# Course_Design.net
KiCad netlist of a schematic drawn in Altium Designer
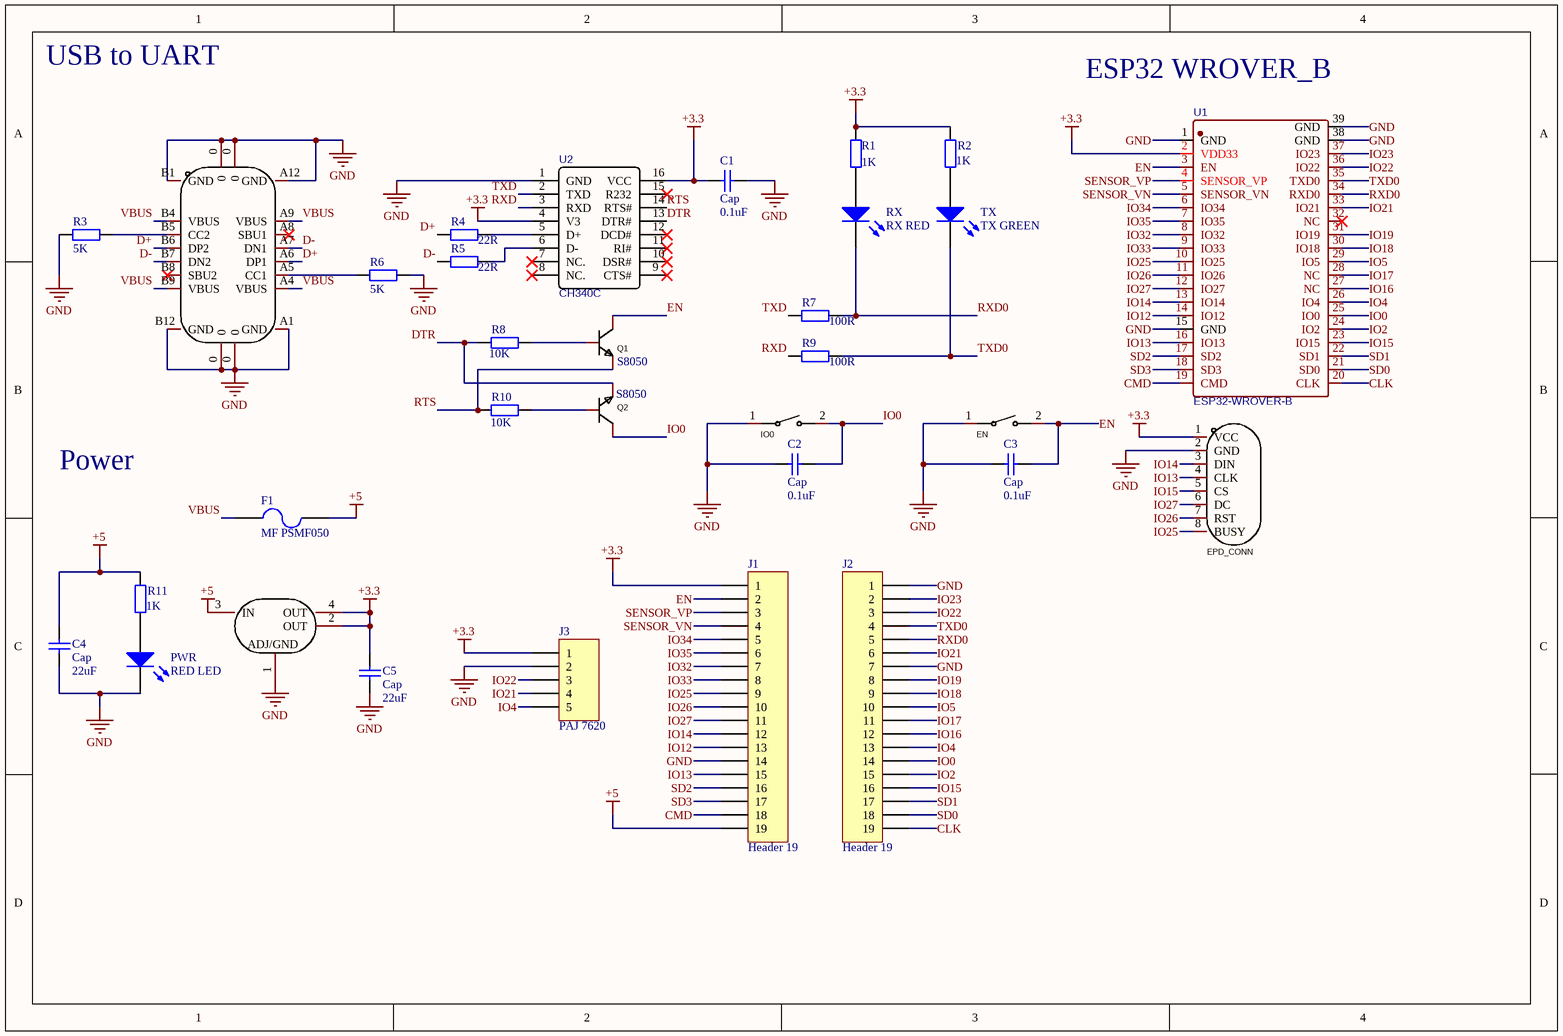
[diagram p0: Course Design.SchDoc]

(export (version "E")
  (design (tool "Eeschema 10.0.6"))
  (components
    (comp (ref "C1")
      (value "Cap")
      (footprint "电容:0805C")
      (description "Capacitor")
      (fields (field (name "ALTIUM_VALUE") "0.1uF") (field (name "PUBLISHER") "Altium Limited"))
      (libsource (lib "Miscellaneous Devices") (part "Cap"))
    )
    (comp (ref "C2")
      (value "Cap")
      (footprint "电容:0805C")
      (description "Capacitor")
      (fields (field (name "ALTIUM_VALUE") "0.1uF") (field (name "PUBLISHER") "Altium Limited"))
      (libsource (lib "Miscellaneous Devices") (part "Cap"))
    )
    (comp (ref "C3")
      (value "Cap")
      (footprint "电容:0805C")
      (description "Capacitor")
      (fields (field (name "ALTIUM_VALUE") "0.1uF") (field (name "PUBLISHER") "Altium Limited"))
      (libsource (lib "Miscellaneous Devices") (part "Cap"))
    )
    (comp (ref "C4")
      (value "Cap")
      (footprint "电容:1206C")
      (description "Capacitor")
      (fields (field (name "ALTIUM_VALUE") "22uF") (field (name "PUBLISHER") "Altium Limited"))
      (libsource (lib "Miscellaneous Devices") (part "Cap"))
    )
    (comp (ref "C5")
      (value "Cap")
      (footprint "电容:1206C")
      (description "Capacitor")
      (fields (field (name "ALTIUM_VALUE") "22uF") (field (name "PUBLISHER") "Altium Limited"))
      (libsource (lib "Miscellaneous Devices") (part "Cap"))
    )
    (comp (ref "EN")
      (value "K2-1107ST-A4DW-06_C118141")
      (footprint "KEY-SMD_L6.2-W3.6-LS8.0")
      (fields (field (name "MANUFACTURER") "韩国韩荣") (field (name "MANUFACTURER PART") "K2-1107ST-A4DW-06"))
      (libsource (lib "Schlib1") (part "K2-1107ST-A4DW-06_C118141"))
    )
    (comp (ref "EPD_CONN")
      (value "X2012WV-08-N0SN")
      (footprint "CONN-TH_X2012WV-08-N0SN")
      (fields (field (name "MANUFACTURER") "XKB Connectivity(中国星坤)"))
      (libsource (lib "Schlib1") (part "X2012WV-08-N0SN"))
    )
    (comp (ref "F1")
      (value "MF PSMF050")
      (footprint "0805")
      (description "Fuse")
      (fields (field (name "PUBLISHER") "Altium Limited"))
      (libsource (lib "Miscellaneous Devices") (part "Fuse 2"))
    )
    (comp (ref "IO0")
      (value "K2-1107ST-A4DW-06_C118141")
      (footprint "KEY-SMD_L6.2-W3.6-LS8.0")
      (fields (field (name "MANUFACTURER") "韩国韩荣") (field (name "MANUFACTURER PART") "K2-1107ST-A4DW-06"))
      (libsource (lib "Schlib1") (part "K2-1107ST-A4DW-06_C118141"))
    )
    (comp (ref "J1")
      (value "Header 19")
      (footprint "HDR1X19")
      (description "Header, 19-Pin")
      (fields (field (name "PUBLISHER") "Altium Limited"))
      (libsource (lib "Miscellaneous Connectors") (part "Header 19"))
    )
    (comp (ref "J2")
      (value "Header 19")
      (footprint "HDR1X19")
      (description "Header, 19-Pin")
      (fields (field (name "PUBLISHER") "Altium Limited"))
      (libsource (lib "") (part "Header 19_1"))
    )
    (comp (ref "J3")
      (value "PAJ 7620")
      (footprint "PAJ7620")
      (description "Header, 5-Pin")
      (fields (field (name "PUBLISHER") "Altium Limited"))
      (libsource (lib "Miscellaneous Connectors") (part "Header 5"))
    )
    (comp (ref "PWR")
      (value "RED LED")
      (footprint "0805D")
      (description "Typical INFRARED GaAs LED")
      (fields (field (name "PUBLISHER") "Altium Limited"))
      (libsource (lib "Miscellaneous Devices") (part "LED0"))
    )
    (comp (ref "Q1")
      (value "S8050")
      (footprint "SOT23_N")
      (fields (field (name "MANUFACTURER") "Doeshare(德芯)"))
      (libsource (lib "Schlib1") (part "S8050"))
    )
    (comp (ref "Q2")
      (value "S8050")
      (footprint "SOT23_N")
      (fields (field (name "MANUFACTURER") "Doeshare(德芯)"))
      (libsource (lib "Schlib1") (part "S8050"))
    )
    (comp (ref "R1")
      (value "1K")
      (footprint "0805R")
      (description "Resistor")
      (fields (field (name "Comment") "Res2") (field (name "PUBLISHER") "Altium Limited"))
      (libsource (lib "Miscellaneous Devices") (part "Res2"))
    )
    (comp (ref "R2")
      (value "1K")
      (footprint "0805R")
      (description "Resistor")
      (fields (field (name "Comment") "Res2") (field (name "PUBLISHER") "Altium Limited"))
      (libsource (lib "Miscellaneous Devices") (part "Res2"))
    )
    (comp (ref "R3")
      (value "5K")
      (footprint "0805R")
      (description "Resistor")
      (fields (field (name "Comment") "Res2") (field (name "PUBLISHER") "Altium Limited"))
      (libsource (lib "") (part "Res2_1"))
    )
    (comp (ref "R4")
      (value "22R")
      (footprint "0805R")
      (description "Resistor")
      (fields (field (name "Comment") "Res2") (field (name "PUBLISHER") "Altium Limited"))
      (libsource (lib "") (part "Res2_1"))
    )
    (comp (ref "R5")
      (value "22R")
      (footprint "0805R")
      (description "Resistor")
      (fields (field (name "Comment") "Res2") (field (name "PUBLISHER") "Altium Limited"))
      (libsource (lib "") (part "Res2_1"))
    )
    (comp (ref "R6")
      (value "5K")
      (footprint "0805R")
      (description "Resistor")
      (fields (field (name "Comment") "Res2") (field (name "PUBLISHER") "Altium Limited"))
      (libsource (lib "") (part "Res2_1"))
    )
    (comp (ref "R7")
      (value "100R")
      (footprint "0805R")
      (description "Resistor")
      (fields (field (name "Comment") "Res2") (field (name "PUBLISHER") "Altium Limited"))
      (libsource (lib "") (part "Res2_1"))
    )
    (comp (ref "R8")
      (value "10K")
      (footprint "0805R")
      (description "Resistor")
      (fields (field (name "Comment") "Res2") (field (name "PUBLISHER") "Altium Limited"))
      (libsource (lib "") (part "Res2_1"))
    )
    (comp (ref "R9")
      (value "100R")
      (footprint "0805R")
      (description "Resistor")
      (fields (field (name "Comment") "Res2") (field (name "PUBLISHER") "Altium Limited"))
      (libsource (lib "") (part "Res2_1"))
    )
    (comp (ref "R10")
      (value "10K")
      (footprint "0805R")
      (description "Resistor")
      (fields (field (name "Comment") "Res2") (field (name "PUBLISHER") "Altium Limited"))
      (libsource (lib "") (part "Res2_1"))
    )
    (comp (ref "R11")
      (value "1K")
      (footprint "0805R")
      (description "Resistor")
      (fields (field (name "Comment") "Res2") (field (name "PUBLISHER") "Altium Limited"))
      (libsource (lib "Miscellaneous Devices") (part "Res2"))
    )
    (comp (ref "RX")
      (value "RX RED")
      (footprint "0805D")
      (description "Typical INFRARED GaAs LED")
      (fields (field (name "PUBLISHER") "Altium Limited"))
      (libsource (lib "Miscellaneous Devices") (part "LED0"))
    )
    (comp (ref "TX")
      (value "TX GREEN")
      (footprint "0805D")
      (description "Typical INFRARED GaAs LED")
      (fields (field (name "PUBLISHER") "Altium Limited"))
      (libsource (lib "Miscellaneous Devices") (part "LED0"))
    )
    (comp (ref "U1")
      (value "ESP32-WROVER-B")
      (footprint "ESP32 WROVER B")
      (fields (field (name "BOM_SUPPLIER PART") "C503591") (field (name "CONTRIBUTOR") "LCSC"))
      (libsource (lib "Schlib1") (part "ESP32-WROVER-B"))
    )
    (comp (ref "U2")
      (value "CH340C")
      (footprint "SOP-16_L10.0")
      (fields (field (name "BOM_SUPPLIER PART") "C84681"))
      (libsource (lib "Schlib1") (part "CH340C"))
    )
    (comp (ref "U3")
      (value "AMS1117-3.3_C2992570")
      (footprint "SOT223_N")
      (fields (field (name "MANUFACTURER") "国芯佳品") (field (name "MANUFACTURER PART") "AMS1117-3.3"))
      (libsource (lib "Schlib1") (part "AMS1117-3.3_C2992570"))
    )
    (comp (ref "USBC1")
      (value "TYPE-C-31-M-12")
      (footprint "USB-C_SMD")
      (fields (field (name "MANUFACTURER") "韩国韩荣"))
      (libsource (lib "Schlib1") (part "TYPE-C-31-M-12"))
    )
  )
  (nets
    (net (code "1") (name "+3.3") (class "Default")
      (node (ref "C1") (pin "1") (pinfunction "1_1") (pintype "passive"))
      (node (ref "C5") (pin "2") (pinfunction "2_2") (pintype "passive"))
      (node (ref "EPD_CONN") (pin "1") (pinfunction "VCC_1") (pintype "passive"))
      (node (ref "J1") (pin "1") (pinfunction "1_1") (pintype "passive"))
      (node (ref "J3") (pin "1") (pinfunction "1_1") (pintype "passive"))
      (node (ref "R1") (pin "2") (pinfunction "2_2") (pintype "passive"))
      (node (ref "R2") (pin "2") (pinfunction "2_2") (pintype "passive"))
      (node (ref "U1") (pin "2") (pinfunction "VDD33_2") (pintype "passive"))
      (node (ref "U2") (pin "16") (pinfunction "VCC_16") (pintype "passive"))
      (node (ref "U2") (pin "4") (pinfunction "V3_4") (pintype "passive"))
      (node (ref "U3") (pin "2") (pinfunction "OUT_2") (pintype "passive"))
      (node (ref "U3") (pin "4") (pinfunction "OUT_4") (pintype "passive"))
    )
    (net (code "2") (name "+5") (class "Default")
      (node (ref "C4") (pin "2") (pinfunction "2_2") (pintype "passive"))
      (node (ref "F1") (pin "2") (pinfunction "2_2") (pintype "passive"))
      (node (ref "J1") (pin "19") (pinfunction "19_19") (pintype "passive"))
      (node (ref "R11") (pin "2") (pinfunction "2_2") (pintype "passive"))
      (node (ref "U3") (pin "3") (pinfunction "IN_3") (pintype "passive"))
    )
    (net (code "3") (name "/CLK") (class "Default")
      (node (ref "J2") (pin "19") (pinfunction "19_19") (pintype "passive"))
      (node (ref "U1") (pin "20") (pinfunction "CLK_20") (pintype "passive"))
    )
    (net (code "4") (name "/CMD") (class "Default")
      (node (ref "J1") (pin "18") (pinfunction "18_18") (pintype "passive"))
      (node (ref "U1") (pin "19") (pinfunction "CMD_19") (pintype "passive"))
    )
    (net (code "5") (name "/D+") (class "Default")
      (node (ref "R4") (pin "1") (pinfunction "1_1") (pintype "passive"))
      (node (ref "USBC1") (pin "A6") (pinfunction "DP1_A6") (pintype "passive"))
      (node (ref "USBC1") (pin "B6") (pinfunction "DP2_B6") (pintype "passive"))
    )
    (net (code "6") (name "/D-") (class "Default")
      (node (ref "R5") (pin "1") (pinfunction "1_1") (pintype "passive"))
      (node (ref "USBC1") (pin "A7") (pinfunction "DN1_A7") (pintype "passive"))
      (node (ref "USBC1") (pin "B7") (pinfunction "DN2_B7") (pintype "passive"))
    )
    (net (code "7") (name "/DTR") (class "Default")
      (node (ref "Q2") (pin "2") (pinfunction "E_2") (pintype "passive"))
      (node (ref "R8") (pin "1") (pinfunction "1_1") (pintype "passive"))
      (node (ref "U2") (pin "13") (pinfunction "DTR#_13") (pintype "passive"))
    )
    (net (code "8") (name "/EN") (class "Default")
      (node (ref "C3") (pin "2") (pinfunction "2_2") (pintype "passive"))
      (node (ref "EN") (pin "2") (pinfunction "2_2") (pintype "passive"))
      (node (ref "J1") (pin "2") (pinfunction "2_2") (pintype "passive"))
      (node (ref "Q1") (pin "3") (pinfunction "C_3") (pintype "passive"))
      (node (ref "U1") (pin "3") (pinfunction "EN_3") (pintype "passive"))
    )
    (net (code "9") (name "/IO0") (class "Default")
      (node (ref "C2") (pin "2") (pinfunction "2_2") (pintype "passive"))
      (node (ref "IO0") (pin "2") (pinfunction "2_2") (pintype "passive"))
      (node (ref "J2") (pin "14") (pinfunction "14_14") (pintype "passive"))
      (node (ref "Q2") (pin "3") (pinfunction "C_3") (pintype "passive"))
      (node (ref "U1") (pin "25") (pinfunction "IO0_25") (pintype "passive"))
    )
    (net (code "10") (name "/IO2") (class "Default")
      (node (ref "J2") (pin "15") (pinfunction "15_15") (pintype "passive"))
      (node (ref "U1") (pin "24") (pinfunction "IO2_24") (pintype "passive"))
    )
    (net (code "11") (name "/IO4") (class "Default")
      (node (ref "J2") (pin "13") (pinfunction "13_13") (pintype "passive"))
      (node (ref "J3") (pin "5") (pinfunction "5_5") (pintype "passive"))
      (node (ref "U1") (pin "26") (pinfunction "IO4_26") (pintype "passive"))
    )
    (net (code "12") (name "/IO5") (class "Default")
      (node (ref "J2") (pin "10") (pinfunction "10_10") (pintype "passive"))
      (node (ref "U1") (pin "29") (pinfunction "IO5_29") (pintype "passive"))
    )
    (net (code "13") (name "/IO12") (class "Default")
      (node (ref "J1") (pin "13") (pinfunction "13_13") (pintype "passive"))
      (node (ref "U1") (pin "14") (pinfunction "IO12_14") (pintype "passive"))
    )
    (net (code "14") (name "/IO13") (class "Default")
      (node (ref "EPD_CONN") (pin "4") (pinfunction "CLK_4") (pintype "passive"))
      (node (ref "J1") (pin "15") (pinfunction "15_15") (pintype "passive"))
      (node (ref "U1") (pin "16") (pinfunction "IO13_16") (pintype "passive"))
    )
    (net (code "15") (name "/IO14") (class "Default")
      (node (ref "EPD_CONN") (pin "3") (pinfunction "DIN_3") (pintype "passive"))
      (node (ref "J1") (pin "12") (pinfunction "12_12") (pintype "passive"))
      (node (ref "U1") (pin "13") (pinfunction "IO14_13") (pintype "passive"))
    )
    (net (code "16") (name "/IO15") (class "Default")
      (node (ref "EPD_CONN") (pin "5") (pinfunction "CS_5") (pintype "passive"))
      (node (ref "J2") (pin "16") (pinfunction "16_16") (pintype "passive"))
      (node (ref "U1") (pin "23") (pinfunction "IO15_23") (pintype "passive"))
    )
    (net (code "17") (name "/IO16") (class "Default")
      (node (ref "J2") (pin "12") (pinfunction "12_12") (pintype "passive"))
      (node (ref "U1") (pin "27") (pinfunction "NC_27") (pintype "passive"))
    )
    (net (code "18") (name "/IO17") (class "Default")
      (node (ref "J2") (pin "11") (pinfunction "11_11") (pintype "passive"))
      (node (ref "U1") (pin "28") (pinfunction "NC_28") (pintype "passive"))
    )
    (net (code "19") (name "/IO18") (class "Default")
      (node (ref "J2") (pin "9") (pinfunction "9_9") (pintype "passive"))
      (node (ref "U1") (pin "30") (pinfunction "IO18_30") (pintype "passive"))
    )
    (net (code "20") (name "/IO19") (class "Default")
      (node (ref "J2") (pin "8") (pinfunction "8_8") (pintype "passive"))
      (node (ref "U1") (pin "31") (pinfunction "IO19_31") (pintype "passive"))
    )
    (net (code "21") (name "/IO21") (class "Default")
      (node (ref "J2") (pin "6") (pinfunction "6_6") (pintype "passive"))
      (node (ref "J3") (pin "4") (pinfunction "4_4") (pintype "passive"))
      (node (ref "U1") (pin "33") (pinfunction "IO21_33") (pintype "passive"))
    )
    (net (code "22") (name "/IO22") (class "Default")
      (node (ref "J2") (pin "3") (pinfunction "3_3") (pintype "passive"))
      (node (ref "J3") (pin "3") (pinfunction "3_3") (pintype "passive"))
      (node (ref "U1") (pin "36") (pinfunction "IO22_36") (pintype "passive"))
    )
    (net (code "23") (name "/IO23") (class "Default")
      (node (ref "J2") (pin "2") (pinfunction "2_2") (pintype "passive"))
      (node (ref "U1") (pin "37") (pinfunction "IO23_37") (pintype "passive"))
    )
    (net (code "24") (name "/IO25") (class "Default")
      (node (ref "EPD_CONN") (pin "8") (pinfunction "BUSY_8") (pintype "passive"))
      (node (ref "J1") (pin "9") (pinfunction "9_9") (pintype "passive"))
      (node (ref "U1") (pin "10") (pinfunction "IO25_10") (pintype "passive"))
    )
    (net (code "25") (name "/IO26") (class "Default")
      (node (ref "EPD_CONN") (pin "7") (pinfunction "RST_7") (pintype "passive"))
      (node (ref "J1") (pin "10") (pinfunction "10_10") (pintype "passive"))
      (node (ref "U1") (pin "11") (pinfunction "IO26_11") (pintype "passive"))
    )
    (net (code "26") (name "/IO27") (class "Default")
      (node (ref "EPD_CONN") (pin "6") (pinfunction "DC_6") (pintype "passive"))
      (node (ref "J1") (pin "11") (pinfunction "11_11") (pintype "passive"))
      (node (ref "U1") (pin "12") (pinfunction "IO27_12") (pintype "passive"))
    )
    (net (code "27") (name "/IO32") (class "Default")
      (node (ref "J1") (pin "7") (pinfunction "7_7") (pintype "passive"))
      (node (ref "U1") (pin "8") (pinfunction "IO32_8") (pintype "passive"))
    )
    (net (code "28") (name "/IO33") (class "Default")
      (node (ref "J1") (pin "8") (pinfunction "8_8") (pintype "passive"))
      (node (ref "U1") (pin "9") (pinfunction "IO33_9") (pintype "passive"))
    )
    (net (code "29") (name "/IO34") (class "Default")
      (node (ref "J1") (pin "5") (pinfunction "5_5") (pintype "passive"))
      (node (ref "U1") (pin "6") (pinfunction "IO34_6") (pintype "passive"))
    )
    (net (code "30") (name "/IO35") (class "Default")
      (node (ref "J1") (pin "6") (pinfunction "6_6") (pintype "passive"))
      (node (ref "U1") (pin "7") (pinfunction "IO35_7") (pintype "passive"))
    )
    (net (code "31") (name "/RTS") (class "Default")
      (node (ref "Q1") (pin "2") (pinfunction "E_2") (pintype "passive"))
      (node (ref "R10") (pin "1") (pinfunction "1_1") (pintype "passive"))
      (node (ref "U2") (pin "14") (pinfunction "RTS#_14") (pintype "passive"))
    )
    (net (code "32") (name "/RXD") (class "Default")
      (node (ref "R9") (pin "1") (pinfunction "1_1") (pintype "passive"))
      (node (ref "U2") (pin "3") (pinfunction "RXD_3") (pintype "passive"))
    )
    (net (code "33") (name "/RXD0") (class "Default")
      (node (ref "J2") (pin "5") (pinfunction "5_5") (pintype "passive"))
      (node (ref "R7") (pin "2") (pinfunction "2_2") (pintype "passive"))
      (node (ref "RX") (pin "2") (pinfunction "K_2") (pintype "passive"))
      (node (ref "U1") (pin "34") (pinfunction "RXD0_34") (pintype "passive"))
    )
    (net (code "34") (name "/SD0") (class "Default")
      (node (ref "J2") (pin "18") (pinfunction "18_18") (pintype "passive"))
      (node (ref "U1") (pin "21") (pinfunction "SD0_21") (pintype "passive"))
    )
    (net (code "35") (name "/SD1") (class "Default")
      (node (ref "J2") (pin "17") (pinfunction "17_17") (pintype "passive"))
      (node (ref "U1") (pin "22") (pinfunction "SD1_22") (pintype "passive"))
    )
    (net (code "36") (name "/SD2") (class "Default")
      (node (ref "J1") (pin "16") (pinfunction "16_16") (pintype "passive"))
      (node (ref "U1") (pin "17") (pinfunction "SD2_17") (pintype "passive"))
    )
    (net (code "37") (name "/SD3") (class "Default")
      (node (ref "J1") (pin "17") (pinfunction "17_17") (pintype "passive"))
      (node (ref "U1") (pin "18") (pinfunction "SD3_18") (pintype "passive"))
    )
    (net (code "38") (name "/SENSOR_VN") (class "Default")
      (node (ref "J1") (pin "4") (pinfunction "4_4") (pintype "passive"))
      (node (ref "U1") (pin "5") (pinfunction "SENSOR_VN_5") (pintype "passive"))
    )
    (net (code "39") (name "/SENSOR_VP") (class "Default")
      (node (ref "J1") (pin "3") (pinfunction "3_3") (pintype "passive"))
      (node (ref "U1") (pin "4") (pinfunction "SENSOR_VP_4") (pintype "passive"))
    )
    (net (code "40") (name "/TXD") (class "Default")
      (node (ref "R7") (pin "1") (pinfunction "1_1") (pintype "passive"))
      (node (ref "U2") (pin "2") (pinfunction "TXD_2") (pintype "passive"))
    )
    (net (code "41") (name "/TXD0") (class "Default")
      (node (ref "J2") (pin "4") (pinfunction "4_4") (pintype "passive"))
      (node (ref "R9") (pin "2") (pinfunction "2_2") (pintype "passive"))
      (node (ref "TX") (pin "2") (pinfunction "K_2") (pintype "passive"))
      (node (ref "U1") (pin "35") (pinfunction "TXD0_35") (pintype "passive"))
    )
    (net (code "42") (name "/VBUS") (class "Default")
      (node (ref "F1") (pin "1") (pinfunction "1_1") (pintype "passive"))
      (node (ref "USBC1") (pin "A4") (pinfunction "VBUS_A4") (pintype "passive"))
      (node (ref "USBC1") (pin "A9") (pinfunction "VBUS_A9") (pintype "passive"))
      (node (ref "USBC1") (pin "B4") (pinfunction "VBUS_B4") (pintype "passive"))
      (node (ref "USBC1") (pin "B9") (pinfunction "VBUS_B9") (pintype "passive"))
    )
    (net (code "43") (name "GND") (class "Default")
      (node (ref "C1") (pin "2") (pinfunction "2_2") (pintype "passive"))
      (node (ref "C2") (pin "1") (pinfunction "1_1") (pintype "passive"))
      (node (ref "C3") (pin "1") (pinfunction "1_1") (pintype "passive"))
      (node (ref "C4") (pin "1") (pinfunction "1_1") (pintype "passive"))
      (node (ref "C5") (pin "1") (pinfunction "1_1") (pintype "passive"))
      (node (ref "EN") (pin "1") (pinfunction "1_1") (pintype "passive"))
      (node (ref "EPD_CONN") (pin "2") (pinfunction "GND_2") (pintype "passive"))
      (node (ref "IO0") (pin "1") (pinfunction "1_1") (pintype "passive"))
      (node (ref "J1") (pin "14") (pinfunction "14_14") (pintype "passive"))
      (node (ref "J2") (pin "1") (pinfunction "1_1") (pintype "passive"))
      (node (ref "J2") (pin "7") (pinfunction "7_7") (pintype "passive"))
      (node (ref "J3") (pin "2") (pinfunction "2_2") (pintype "passive"))
      (node (ref "PWR") (pin "2") (pinfunction "K_2") (pintype "passive"))
      (node (ref "R3") (pin "1") (pinfunction "1_1") (pintype "passive"))
      (node (ref "R6") (pin "2") (pinfunction "2_2") (pintype "passive"))
      (node (ref "U1") (pin "1") (pinfunction "GND_1") (pintype "passive"))
      (node (ref "U1") (pin "15") (pinfunction "GND_15") (pintype "passive"))
      (node (ref "U1") (pin "38") (pinfunction "GND_38") (pintype "passive"))
      (node (ref "U1") (pin "39") (pinfunction "GND_39") (pintype "passive"))
      (node (ref "U2") (pin "1") (pinfunction "GND_1") (pintype "passive"))
      (node (ref "U3") (pin "1") (pinfunction "ADJ/GND_1") (pintype "passive"))
      (node (ref "USBC1") (pin "0") (pinfunction "0_0") (pintype "passive"))
      (node (ref "USBC1") (pin "A1") (pinfunction "GND_A1") (pintype "passive"))
      (node (ref "USBC1") (pin "A12") (pinfunction "GND_A12") (pintype "passive"))
      (node (ref "USBC1") (pin "B1") (pinfunction "GND_B1") (pintype "passive"))
      (node (ref "USBC1") (pin "B12") (pinfunction "GND_B12") (pintype "passive"))
    )
    (net (code "44") (name "Net-(PWR-A)") (class "Default")
      (node (ref "PWR") (pin "1") (pinfunction "A_1") (pintype "passive"))
      (node (ref "R11") (pin "1") (pinfunction "1_1") (pintype "passive"))
    )
    (net (code "45") (name "Net-(Q1-B)") (class "Default")
      (node (ref "Q1") (pin "1") (pinfunction "B_1") (pintype "passive"))
      (node (ref "R8") (pin "2") (pinfunction "2_2") (pintype "passive"))
    )
    (net (code "46") (name "Net-(Q2-B)") (class "Default")
      (node (ref "Q2") (pin "1") (pinfunction "B_1") (pintype "passive"))
      (node (ref "R10") (pin "2") (pinfunction "2_2") (pintype "passive"))
    )
    (net (code "47") (name "Net-(RX-A)") (class "Default")
      (node (ref "R1") (pin "1") (pinfunction "1_1") (pintype "passive"))
      (node (ref "RX") (pin "1") (pinfunction "A_1") (pintype "passive"))
    )
    (net (code "48") (name "Net-(TX-A)") (class "Default")
      (node (ref "R2") (pin "1") (pinfunction "1_1") (pintype "passive"))
      (node (ref "TX") (pin "1") (pinfunction "A_1") (pintype "passive"))
    )
    (net (code "49") (name "Net-(U2-D+)") (class "Default")
      (node (ref "R4") (pin "2") (pinfunction "2_2") (pintype "passive"))
      (node (ref "U2") (pin "5") (pinfunction "D+_5") (pintype "passive"))
    )
    (net (code "50") (name "Net-(U2-D-)") (class "Default")
      (node (ref "R5") (pin "2") (pinfunction "2_2") (pintype "passive"))
      (node (ref "U2") (pin "6") (pinfunction "D-_6") (pintype "passive"))
    )
    (net (code "51") (name "Net-(USBC1-CC1)") (class "Default")
      (node (ref "R6") (pin "1") (pinfunction "1_1") (pintype "passive"))
      (node (ref "USBC1") (pin "A5") (pinfunction "CC1_A5") (pintype "passive"))
    )
    (net (code "52") (name "Net-(USBC1-CC2)") (class "Default")
      (node (ref "R3") (pin "2") (pinfunction "2_2") (pintype "passive"))
      (node (ref "USBC1") (pin "B5") (pinfunction "CC2_B5") (pintype "passive"))
    )
    (net (code "53") (name "unconnected-(U1-NC-Pad32)") (class "Default")
      (node (ref "U1") (pin "32") (pinfunction "NC_32") (pintype "passive+no_connect"))
    )
    (net (code "54") (name "unconnected-(U2-CTS#-Pad9)") (class "Default")
      (node (ref "U2") (pin "9") (pinfunction "CTS#_9") (pintype "passive+no_connect"))
    )
    (net (code "55") (name "unconnected-(U2-DCD#-Pad12)") (class "Default")
      (node (ref "U2") (pin "12") (pinfunction "DCD#_12") (pintype "passive+no_connect"))
    )
    (net (code "56") (name "unconnected-(U2-DSR#-Pad10)") (class "Default")
      (node (ref "U2") (pin "10") (pinfunction "DSR#_10") (pintype "passive+no_connect"))
    )
    (net (code "57") (name "unconnected-(U2-NC.-Pad7)") (class "Default")
      (node (ref "U2") (pin "7") (pinfunction "NC._7") (pintype "passive+no_connect"))
    )
    (net (code "58") (name "unconnected-(U2-NC.-Pad8)") (class "Default")
      (node (ref "U2") (pin "8") (pinfunction "NC._8") (pintype "passive+no_connect"))
    )
    (net (code "59") (name "unconnected-(U2-R232-Pad15)") (class "Default")
      (node (ref "U2") (pin "15") (pinfunction "R232_15") (pintype "passive+no_connect"))
    )
    (net (code "60") (name "unconnected-(U2-RI#-Pad11)") (class "Default")
      (node (ref "U2") (pin "11") (pinfunction "RI#_11") (pintype "passive+no_connect"))
    )
    (net (code "61") (name "unconnected-(USBC1-SBU1-PadA8)") (class "Default")
      (node (ref "USBC1") (pin "A8") (pinfunction "SBU1_A8") (pintype "passive+no_connect"))
    )
    (net (code "62") (name "unconnected-(USBC1-SBU2-PadB8)") (class "Default")
      (node (ref "USBC1") (pin "B8") (pinfunction "SBU2_B8") (pintype "passive+no_connect"))
    )
  )
)
